# Load-Transient_Tool.net
KiCad netlist of a schematic drawn in Altium Designer
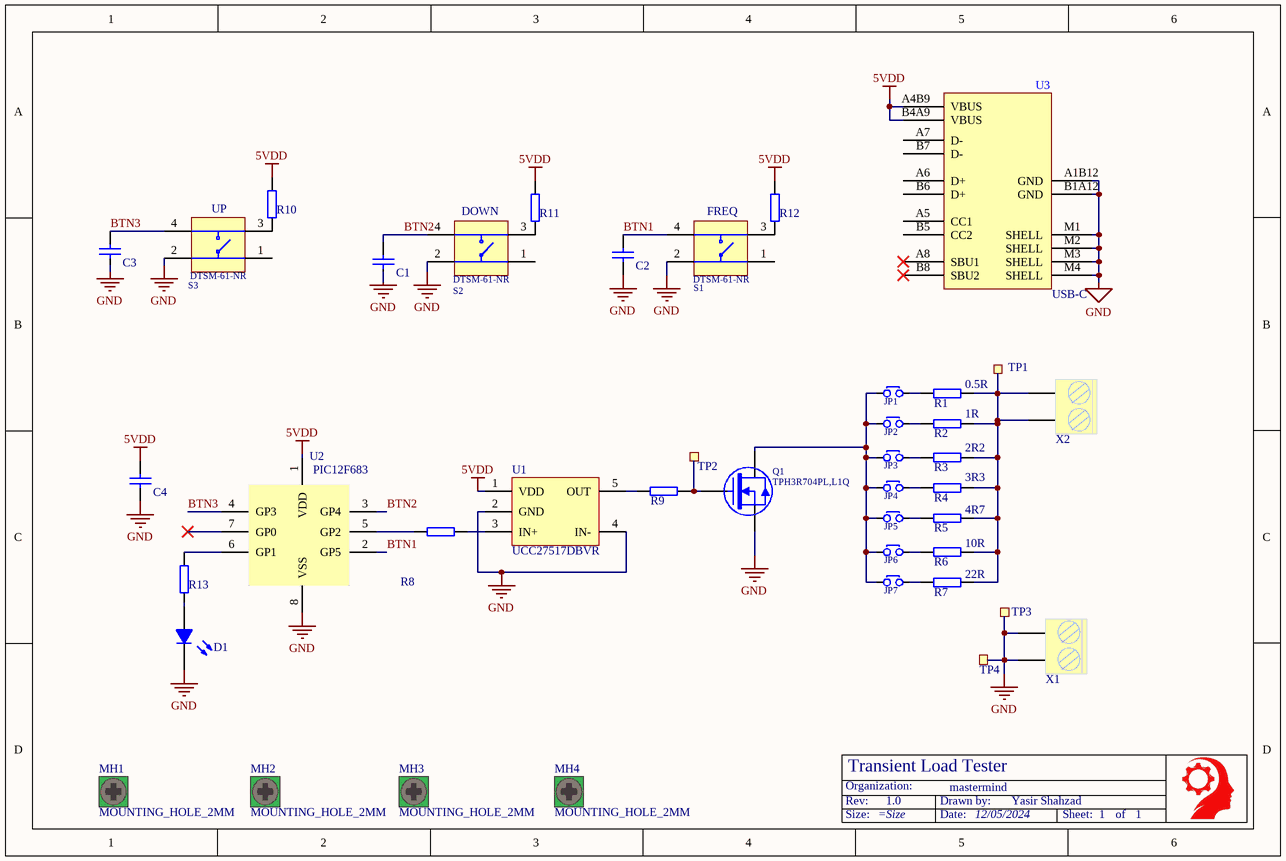
[diagram p0: Load-Transient_Tool.SchDoc]

(export (version "E")
  (design (tool "Eeschema 10.0.6"))
  (components
    (comp (ref "*")
      (value "TitleBlock")
      (description "Title Block for Schematic Sheets")
      (libsource (lib "Mastermind Devices") (part "TitleBlock"))
    )
    (comp (ref "C1")
      (value "4.7nF")
      (footprint "C0603")
      (description "Capacitor, X5R, ±10%, 6.3V")
      (fields
        (field (name "PART NUMBER") "C0603-N.C.")
        (field (name "MANUFACTURER") "N.A.")
        (field (name "PUBLISHER") "Nordic Semiconductor")
      )
      (libsource (lib "Mastermind Devices") (part "Cap_0603"))
    )
    (comp (ref "C2")
      (value "4.7nF")
      (footprint "C0603")
      (description "Capacitor, X5R, ±10%, 6.3V")
      (fields
        (field (name "PART NUMBER") "C0603-N.C.")
        (field (name "MANUFACTURER") "N.A.")
        (field (name "PUBLISHER") "Nordic Semiconductor")
      )
      (libsource (lib "Mastermind Devices") (part "Cap_0603"))
    )
    (comp (ref "C3")
      (value "4.7nF")
      (footprint "C0603")
      (description "Capacitor, X5R, ±10%, 6.3V")
      (fields
        (field (name "PART NUMBER") "C0603-N.C.")
        (field (name "MANUFACTURER") "N.A.")
        (field (name "PUBLISHER") "Nordic Semiconductor")
      )
      (libsource (lib "Mastermind Devices") (part "Cap_0603"))
    )
    (comp (ref "C4")
      (value "N.C")
      (footprint "C0805")
      (description "Capacitor, X5R, ±10%, 6.3V")
      (fields (field (name "MANUFACTURER") "N.A."))
      (libsource (lib "Mastermind Devices") (part "Cap_0805"))
    )
    (comp (ref "D1")
      (value "LED")
      (footprint "CHIPLED_0603")
      (description "SMD lamp beads")
      (libsource (lib "Mastermind Devices") (part "LEDCHIP-LED0603"))
    )
    (comp (ref "JP1")
      (value "Jumper, 2-Pin")
      (footprint "JUMPER-2PIN")
      (libsource (lib "Mastermind Devices") (part "Jumper, 2-Pin_TH"))
    )
    (comp (ref "JP2")
      (value "Jumper, 2-Pin")
      (footprint "JUMPER-2PIN")
      (libsource (lib "Mastermind Devices") (part "Jumper, 2-Pin_TH"))
    )
    (comp (ref "JP3")
      (value "Jumper, 2-Pin")
      (footprint "JUMPER-2PIN")
      (libsource (lib "Mastermind Devices") (part "Jumper, 2-Pin_TH"))
    )
    (comp (ref "JP4")
      (value "Jumper, 2-Pin")
      (footprint "JUMPER-2PIN")
      (libsource (lib "Mastermind Devices") (part "Jumper, 2-Pin_TH"))
    )
    (comp (ref "JP5")
      (value "Jumper, 2-Pin")
      (footprint "JUMPER-2PIN")
      (libsource (lib "Mastermind Devices") (part "Jumper, 2-Pin_TH"))
    )
    (comp (ref "JP6")
      (value "Jumper, 2-Pin")
      (footprint "JUMPER-2PIN")
      (libsource (lib "Mastermind Devices") (part "Jumper, 2-Pin_TH"))
    )
    (comp (ref "JP7")
      (value "Jumper, 2-Pin")
      (footprint "JUMPER-2PIN")
      (libsource (lib "Mastermind Devices") (part "Jumper, 2-Pin_TH"))
    )
    (comp (ref "MH1")
      (value "MOUNTING_HOLE_2MM")
      (footprint "MOUNTINGHOLE_2.5_PLATED")
      (libsource (lib "Mastermind Devices") (part "MOUNTING_HOLE_2.5MM_PLATED"))
    )
    (comp (ref "MH2")
      (value "MOUNTING_HOLE_2MM")
      (footprint "MOUNTINGHOLE_2.5_PLATED")
      (libsource (lib "Mastermind Devices") (part "MOUNTING_HOLE_2.5MM_PLATED"))
    )
    (comp (ref "MH3")
      (value "MOUNTING_HOLE_2MM")
      (footprint "MOUNTINGHOLE_2.5_PLATED")
      (libsource (lib "Mastermind Devices") (part "MOUNTING_HOLE_2.5MM_PLATED"))
    )
    (comp (ref "MH4")
      (value "MOUNTING_HOLE_2MM")
      (footprint "MOUNTINGHOLE_2.5_PLATED")
      (libsource (lib "Mastermind Devices") (part "MOUNTING_HOLE_2.5MM_PLATED"))
    )
    (comp (ref "Q1")
      (value "TPH3R704PL,L1Q")
      (footprint "POWERDI3333-8_L3.3-W3.3-P0.65-BL")
      (description "N Channel Mosfet 40V 92A dfn-8")
      (libsource (lib "Mastermind Devices") (part "MOSFET-TPH3R704PL_1"))
    )
    (comp (ref "R1")
      (value "0.5Ω")
      (footprint "R2512")
      (description "Resistor")
      (libsource (lib "Mastermind Devices") (part "Res_2512"))
    )
    (comp (ref "R2")
      (value "1Ω")
      (footprint "R2512")
      (description "Resistor")
      (libsource (lib "Mastermind Devices") (part "Res_2512"))
    )
    (comp (ref "R3")
      (value "2.2Ω")
      (footprint "R2512")
      (description "Resistor")
      (libsource (lib "Mastermind Devices") (part "Res_2512"))
    )
    (comp (ref "R4")
      (value "3.3Ω")
      (footprint "R2512")
      (description "Resistor")
      (libsource (lib "Mastermind Devices") (part "Res_2512"))
    )
    (comp (ref "R5")
      (value "4.7Ω")
      (footprint "R2512")
      (description "Resistor")
      (libsource (lib "Mastermind Devices") (part "Res_2512"))
    )
    (comp (ref "R6")
      (value "10Ω")
      (footprint "R2512")
      (description "Resistor")
      (libsource (lib "Mastermind Devices") (part "Res_2512"))
    )
    (comp (ref "R7")
      (value "22Ω")
      (footprint "R2512")
      (description "Resistor")
      (libsource (lib "Mastermind Devices") (part "Res_2512"))
    )
    (comp (ref "R8")
      (value "470Ω")
      (footprint "R0603")
      (description "Resistor, ±1%, 0.100W")
      (fields
        (field (name "PART NUMBER") "R0603-N.C.Ω")
        (field (name "MANUFACTURER") "N.A.")
        (field (name "PUBLISHER") "Nordic Semiconductor")
      )
      (libsource (lib "") (part "Res_0603_1"))
    )
    (comp (ref "R9")
      (value "47Ω")
      (footprint "R0603")
      (description "Resistor, ±1%, 0.100W")
      (fields
        (field (name "PART NUMBER") "R0603-N.C.Ω")
        (field (name "MANUFACTURER") "N.A.")
        (field (name "PUBLISHER") "Nordic Semiconductor")
      )
      (libsource (lib "") (part "Res_0603_1"))
    )
    (comp (ref "R10")
      (value "4.7kΩ")
      (footprint "R0603")
      (description "Resistor, ±1%, 0.100W")
      (fields
        (field (name "PART NUMBER") "R0603-N.C.Ω")
        (field (name "MANUFACTURER") "N.A.")
        (field (name "PUBLISHER") "Nordic Semiconductor")
      )
      (libsource (lib "Mastermind Devices") (part "Res_0603"))
    )
    (comp (ref "R11")
      (value "4.7kΩ")
      (footprint "R0603")
      (description "Resistor, ±1%, 0.100W")
      (fields
        (field (name "PART NUMBER") "R0603-N.C.Ω")
        (field (name "MANUFACTURER") "N.A.")
        (field (name "PUBLISHER") "Nordic Semiconductor")
      )
      (libsource (lib "Mastermind Devices") (part "Res_0603"))
    )
    (comp (ref "R12")
      (value "4.7kΩ")
      (footprint "R0603")
      (description "Resistor, ±1%, 0.100W")
      (fields
        (field (name "PART NUMBER") "R0603-N.C.Ω")
        (field (name "MANUFACTURER") "N.A.")
        (field (name "PUBLISHER") "Nordic Semiconductor")
      )
      (libsource (lib "Mastermind Devices") (part "Res_0603"))
    )
    (comp (ref "R13")
      (value "1kΩ")
      (footprint "R0603")
      (description "Resistor, ±1%, 0.100W")
      (fields
        (field (name "PART NUMBER") "R0603-N.C.Ω")
        (field (name "MANUFACTURER") "N.A.")
        (field (name "PUBLISHER") "Nordic Semiconductor")
      )
      (libsource (lib "Mastermind Devices") (part "Res_0603"))
    )
    (comp (ref "S1")
      (value "DTSM-61-NR")
      (footprint "KEY-TH_4P-L6.2-W6.2-P4.50-LS6.5")
      (description "SPNA SMD Keyboard Switch")
      (libsource (lib "Mastermind Devices") (part "SW B3FS"))
    )
    (comp (ref "S2")
      (value "DTSM-61-NR")
      (footprint "KEY-TH_4P-L6.2-W6.2-P4.50-LS6.5")
      (description "SPNA SMD Keyboard Switch")
      (libsource (lib "Mastermind Devices") (part "SW B3FS"))
    )
    (comp (ref "S3")
      (value "DTSM-61-NR")
      (footprint "KEY-TH_4P-L6.2-W6.2-P4.50-LS6.5")
      (description "SPNA SMD Keyboard Switch")
      (libsource (lib "Mastermind Devices") (part "SW B3FS"))
    )
    (comp (ref "TP1")
      (value "TP")
      (footprint "TP_TH_1MM_RED")
      (description "Testpoint, through hole")
      (fields (field (name "PART NUMBER") "Testpoint TH") (field (name "PUBLISHER") "Nordic Semiconductor"))
      (libsource (lib "Mastermind Devices") (part "TESTPAD_TH"))
    )
    (comp (ref "TP2")
      (value "TP")
      (footprint "TP_TH_1MM_YELLOW")
      (description "Testpoint, through hole")
      (fields (field (name "PART NUMBER") "Testpoint TH") (field (name "PUBLISHER") "Nordic Semiconductor"))
      (libsource (lib "Mastermind Devices") (part "TESTPAD_TH"))
    )
    (comp (ref "TP3")
      (value "TP")
      (footprint "TP_TH_1MM_BLACK")
      (description "Testpoint, through hole")
      (fields (field (name "PART NUMBER") "Testpoint TH") (field (name "PUBLISHER") "Nordic Semiconductor"))
      (libsource (lib "Mastermind Devices") (part "TESTPAD_TH"))
    )
    (comp (ref "TP4")
      (value "TP")
      (footprint "TP_TH_1MM_BLACK")
      (description "Testpoint, through hole")
      (fields (field (name "PART NUMBER") "Testpoint TH") (field (name "PUBLISHER") "Nordic Semiconductor"))
      (libsource (lib "") (part "TESTPAD_TH_1"))
    )
    (comp (ref "U1")
      (value "UCC27517DBVR")
      (footprint "SOT23-5L")
      (description "Gate Drive ICs ROHS")
      (fields (field (name "NAME") "UCC27517DBVR"))
      (libsource (lib "Mastermind Devices") (part "UCC27517DBVR"))
    )
    (comp (ref "U2")
      (value "PIC12F683")
      (footprint "DIL08-ROUND")
      (fields (field (name "NAME") "PIC12F683"))
      (libsource (lib "Mastermind Devices") (part "PIC12F683"))
    )
    (comp (ref "U3")
      (value "USB C")
      (footprint "USB_C_CUSB31-CFM2AX-01-X")
      (description "USB Type-C USB 2.0 Connector")
      (libsource (lib "Mastermind Devices") (part "USB_C"))
    )
    (comp (ref "X1")
      (value "Terminal Block 3.5mmPitch: 3,5 mmNumber of pins: 2Created by Rembrandt Electronicswww.rembrandtelectronics.com")
      (footprint "SCREWTERMINAL-5MM-2")
      (libsource (lib "Mastermind Devices") (part "SCREWTERMINAL-H2-5.0"))
    )
    (comp (ref "X2")
      (value "Terminal Block 3.5mmPitch: 3,5 mmNumber of pins: 2Created by Rembrandt Electronicswww.rembrandtelectronics.com")
      (footprint "SCREWTERMINAL-5MM-2")
      (libsource (lib "Mastermind Devices") (part "SCREWTERMINAL-H2-5.0"))
    )
  )
  (nets
    (net (code "1") (name "/BTN1") (class "Default")
      (node (ref "C2") (pin "1") (pinfunction "1_1") (pintype "passive"))
      (node (ref "S1") (pin "4") (pinfunction "4_4") (pintype "passive"))
      (node (ref "U2") (pin "2") (pinfunction "GP5_2") (pintype "passive"))
    )
    (net (code "2") (name "/BTN2") (class "Default")
      (node (ref "C1") (pin "1") (pinfunction "1_1") (pintype "passive"))
      (node (ref "S2") (pin "4") (pinfunction "4_4") (pintype "passive"))
      (node (ref "U2") (pin "3") (pinfunction "GP4_3") (pintype "passive"))
    )
    (net (code "3") (name "/BTN3") (class "Default")
      (node (ref "C3") (pin "1") (pinfunction "1_1") (pintype "passive"))
      (node (ref "S3") (pin "4") (pinfunction "4_4") (pintype "passive"))
      (node (ref "U2") (pin "4") (pinfunction "GP3_4") (pintype "power_in"))
    )
    (net (code "4") (name "5VDD") (class "Default")
      (node (ref "C4") (pin "1") (pinfunction "1_1") (pintype "passive"))
      (node (ref "R10") (pin "1") (pinfunction "1_1") (pintype "passive"))
      (node (ref "R11") (pin "1") (pinfunction "1_1") (pintype "passive"))
      (node (ref "R12") (pin "1") (pinfunction "1_1") (pintype "passive"))
      (node (ref "U1") (pin "1") (pinfunction "VDD_1") (pintype "passive"))
      (node (ref "U2") (pin "1") (pinfunction "VDD_1") (pintype "power_in"))
      (node (ref "U3") (pin "A4B9") (pinfunction "VBUS_A4B9") (pintype "passive"))
      (node (ref "U3") (pin "B4A9") (pinfunction "VBUS_B4A9") (pintype "passive"))
    )
    (net (code "5") (name "GND") (class "Default")
      (node (ref "C1") (pin "2") (pinfunction "2_2") (pintype "passive"))
      (node (ref "C2") (pin "2") (pinfunction "2_2") (pintype "passive"))
      (node (ref "C3") (pin "2") (pinfunction "2_2") (pintype "passive"))
      (node (ref "C4") (pin "2") (pinfunction "2_2") (pintype "passive"))
      (node (ref "D1") (pin "C") (pinfunction "K_C") (pintype "passive"))
      (node (ref "Q1") (pin "2") (pinfunction "S_2") (pintype "passive"))
      (node (ref "S1") (pin "2") (pinfunction "2_2") (pintype "passive"))
      (node (ref "S2") (pin "2") (pinfunction "2_2") (pintype "passive"))
      (node (ref "S3") (pin "2") (pinfunction "2_2") (pintype "passive"))
      (node (ref "TP3") (pin "1") (pinfunction "1_1") (pintype "passive"))
      (node (ref "TP4") (pin "1") (pinfunction "1_1") (pintype "passive"))
      (node (ref "U1") (pin "2") (pinfunction "GND_2") (pintype "passive"))
      (node (ref "U1") (pin "4") (pinfunction "IN-_4") (pintype "power_in"))
      (node (ref "U2") (pin "8") (pinfunction "VSS_8") (pintype "passive"))
      (node (ref "U3") (pin "A1B12") (pinfunction "GND_A1B12") (pintype "passive"))
      (node (ref "U3") (pin "B1A12") (pinfunction "GND_B1A12") (pintype "passive"))
      (node (ref "U3") (pin "M1") (pinfunction "SHELL_M1") (pintype "passive"))
      (node (ref "U3") (pin "M2") (pinfunction "SHELL_M2") (pintype "passive"))
      (node (ref "U3") (pin "M3") (pinfunction "SHELL_M3") (pintype "passive"))
      (node (ref "U3") (pin "M4") (pinfunction "SHELL_M4") (pintype "passive"))
      (node (ref "X1") (pin "1") (pinfunction "1_1") (pintype "passive"))
      (node (ref "X1") (pin "2") (pinfunction "2_2") (pintype "passive"))
    )
    (net (code "6") (name "Net-(D1-PadA)") (class "Default")
      (node (ref "D1") (pin "A") (pinfunction "A_A") (pintype "passive"))
      (node (ref "R13") (pin "2") (pinfunction "2_2") (pintype "passive"))
    )
    (net (code "7") (name "Net-(JP1-Pad2)") (class "Default")
      (node (ref "JP1") (pin "2") (pinfunction "2_2") (pintype "passive"))
      (node (ref "R1") (pin "2") (pinfunction "2_2") (pintype "passive"))
    )
    (net (code "8") (name "Net-(JP2-Pad2)") (class "Default")
      (node (ref "JP2") (pin "2") (pinfunction "2_2") (pintype "passive"))
      (node (ref "R2") (pin "2") (pinfunction "2_2") (pintype "passive"))
    )
    (net (code "9") (name "Net-(JP3-Pad2)") (class "Default")
      (node (ref "JP3") (pin "2") (pinfunction "2_2") (pintype "passive"))
      (node (ref "R3") (pin "2") (pinfunction "2_2") (pintype "passive"))
    )
    (net (code "10") (name "Net-(JP4-Pad2)") (class "Default")
      (node (ref "JP4") (pin "2") (pinfunction "2_2") (pintype "passive"))
      (node (ref "R4") (pin "2") (pinfunction "2_2") (pintype "passive"))
    )
    (net (code "11") (name "Net-(JP5-Pad2)") (class "Default")
      (node (ref "JP5") (pin "2") (pinfunction "2_2") (pintype "passive"))
      (node (ref "R5") (pin "2") (pinfunction "2_2") (pintype "passive"))
    )
    (net (code "12") (name "Net-(JP6-Pad2)") (class "Default")
      (node (ref "JP6") (pin "2") (pinfunction "2_2") (pintype "passive"))
      (node (ref "R6") (pin "2") (pinfunction "2_2") (pintype "passive"))
    )
    (net (code "13") (name "Net-(JP7-Pad2)") (class "Default")
      (node (ref "JP7") (pin "2") (pinfunction "2_2") (pintype "passive"))
      (node (ref "R7") (pin "2") (pinfunction "2_2") (pintype "passive"))
    )
    (net (code "14") (name "Net-(Q1-D)") (class "Default")
      (node (ref "JP1") (pin "1") (pinfunction "1_1") (pintype "passive"))
      (node (ref "JP2") (pin "1") (pinfunction "1_1") (pintype "passive"))
      (node (ref "JP3") (pin "1") (pinfunction "1_1") (pintype "passive"))
      (node (ref "JP4") (pin "1") (pinfunction "1_1") (pintype "passive"))
      (node (ref "JP5") (pin "1") (pinfunction "1_1") (pintype "passive"))
      (node (ref "JP6") (pin "1") (pinfunction "1_1") (pintype "passive"))
      (node (ref "JP7") (pin "1") (pinfunction "1_1") (pintype "passive"))
      (node (ref "Q1") (pin "3") (pinfunction "D_3") (pintype "passive"))
    )
    (net (code "15") (name "Net-(Q1-G)") (class "Default")
      (node (ref "Q1") (pin "1") (pinfunction "G_1") (pintype "passive"))
      (node (ref "R9") (pin "1") (pinfunction "1_1") (pintype "passive"))
      (node (ref "TP2") (pin "1") (pinfunction "1_1") (pintype "passive"))
    )
    (net (code "16") (name "Net-(R1-Pad1)") (class "Default")
      (node (ref "R1") (pin "1") (pinfunction "1_1") (pintype "passive"))
      (node (ref "R2") (pin "1") (pinfunction "1_1") (pintype "passive"))
      (node (ref "R3") (pin "1") (pinfunction "1_1") (pintype "passive"))
      (node (ref "R4") (pin "1") (pinfunction "1_1") (pintype "passive"))
      (node (ref "R5") (pin "1") (pinfunction "1_1") (pintype "passive"))
      (node (ref "R6") (pin "1") (pinfunction "1_1") (pintype "passive"))
      (node (ref "R7") (pin "1") (pinfunction "1_1") (pintype "passive"))
      (node (ref "TP1") (pin "1") (pinfunction "1_1") (pintype "passive"))
      (node (ref "X2") (pin "1") (pinfunction "1_1") (pintype "passive"))
      (node (ref "X2") (pin "2") (pinfunction "2_2") (pintype "passive"))
    )
    (net (code "17") (name "Net-(R10-Pad2)") (class "Default")
      (node (ref "R10") (pin "2") (pinfunction "2_2") (pintype "passive"))
      (node (ref "S3") (pin "3") (pinfunction "3_3") (pintype "passive"))
    )
    (net (code "18") (name "Net-(R11-Pad2)") (class "Default")
      (node (ref "R11") (pin "2") (pinfunction "2_2") (pintype "passive"))
      (node (ref "S2") (pin "3") (pinfunction "3_3") (pintype "passive"))
    )
    (net (code "19") (name "Net-(R12-Pad2)") (class "Default")
      (node (ref "R12") (pin "2") (pinfunction "2_2") (pintype "passive"))
      (node (ref "S1") (pin "3") (pinfunction "3_3") (pintype "passive"))
    )
    (net (code "20") (name "Net-(U1-IN+)") (class "Default")
      (node (ref "R8") (pin "1") (pinfunction "1_1") (pintype "passive"))
      (node (ref "U1") (pin "3") (pinfunction "IN+_3") (pintype "passive"))
    )
    (net (code "21") (name "Net-(U1-OUT)") (class "Default")
      (node (ref "R9") (pin "2") (pinfunction "2_2") (pintype "passive"))
      (node (ref "U1") (pin "5") (pinfunction "OUT_5") (pintype "power_in"))
    )
    (net (code "22") (name "Net-(U2-GP1)") (class "Default")
      (node (ref "R13") (pin "1") (pinfunction "1_1") (pintype "passive"))
      (node (ref "U2") (pin "6") (pinfunction "GP1_6") (pintype "passive"))
    )
    (net (code "23") (name "Net-(U2-GP2)") (class "Default")
      (node (ref "R8") (pin "2") (pinfunction "2_2") (pintype "passive"))
      (node (ref "U2") (pin "5") (pinfunction "GP2_5") (pintype "passive"))
    )
    (net (code "24") (name "unconnected-(MH1-3-PadMOUNT)") (class "Default")
      (node (ref "MH1") (pin "MOUNT") (pinfunction "3_MOUNT") (pintype "passive"))
    )
    (net (code "25") (name "unconnected-(MH2-3-PadMOUNT)") (class "Default")
      (node (ref "MH2") (pin "MOUNT") (pinfunction "3_MOUNT") (pintype "passive"))
    )
    (net (code "26") (name "unconnected-(MH3-3-PadMOUNT)") (class "Default")
      (node (ref "MH3") (pin "MOUNT") (pinfunction "3_MOUNT") (pintype "passive"))
    )
    (net (code "27") (name "unconnected-(MH4-3-PadMOUNT)") (class "Default")
      (node (ref "MH4") (pin "MOUNT") (pinfunction "3_MOUNT") (pintype "passive"))
    )
    (net (code "28") (name "unconnected-(S1-Pad1)") (class "Default")
      (node (ref "S1") (pin "1") (pinfunction "1_1") (pintype "passive"))
    )
    (net (code "29") (name "unconnected-(S2-Pad1)") (class "Default")
      (node (ref "S2") (pin "1") (pinfunction "1_1") (pintype "passive"))
    )
    (net (code "30") (name "unconnected-(S3-Pad1)") (class "Default")
      (node (ref "S3") (pin "1") (pinfunction "1_1") (pintype "passive"))
    )
    (net (code "31") (name "unconnected-(U2-GP0-Pad7)") (class "Default")
      (node (ref "U2") (pin "7") (pinfunction "GP0_7") (pintype "passive+no_connect"))
    )
    (net (code "32") (name "unconnected-(U3-CC1-PadA5)") (class "Default")
      (node (ref "U3") (pin "A5") (pinfunction "CC1_A5") (pintype "passive"))
    )
    (net (code "33") (name "unconnected-(U3-CC2-PadB5)") (class "Default")
      (node (ref "U3") (pin "B5") (pinfunction "CC2_B5") (pintype "passive"))
    )
    (net (code "34") (name "unconnected-(U3-D+-PadA6)") (class "Default")
      (node (ref "U3") (pin "A6") (pinfunction "D+_A6") (pintype "passive"))
    )
    (net (code "35") (name "unconnected-(U3-D+-PadB6)") (class "Default")
      (node (ref "U3") (pin "B6") (pinfunction "D+_B6") (pintype "passive"))
    )
    (net (code "36") (name "unconnected-(U3-D--PadA7)") (class "Default")
      (node (ref "U3") (pin "A7") (pinfunction "D-_A7") (pintype "passive"))
    )
    (net (code "37") (name "unconnected-(U3-D--PadB7)") (class "Default")
      (node (ref "U3") (pin "B7") (pinfunction "D-_B7") (pintype "passive"))
    )
    (net (code "38") (name "unconnected-(U3-SBU1-PadA8)") (class "Default")
      (node (ref "U3") (pin "A8") (pinfunction "SBU1_A8") (pintype "passive+no_connect"))
    )
    (net (code "39") (name "unconnected-(U3-SBU2-PadB8)") (class "Default")
      (node (ref "U3") (pin "B8") (pinfunction "SBU2_B8") (pintype "passive+no_connect"))
    )
  )
)
